# Temperature_Sensor_Rev_2.net
KiCad netlist of a schematic drawn in EAGLE
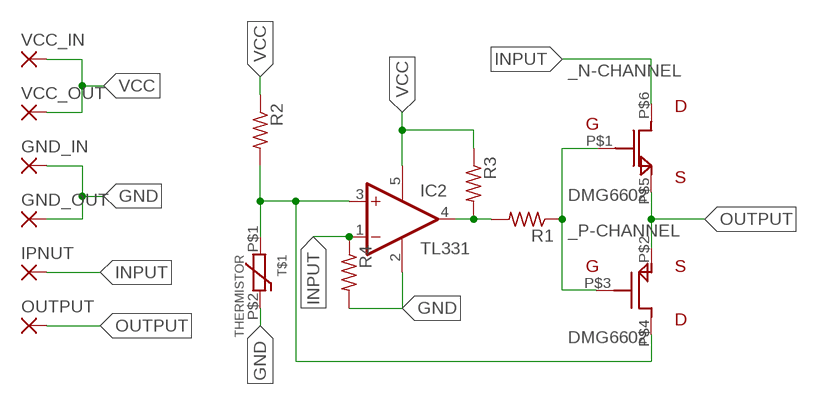
[diagram p0: schematic, sheet 1]

(export (version "E")
  (design (tool "Eeschema 10.0.6"))
  (components
    (comp (ref "GND_IN")
      (value "1,6/0,8")
      (footprint "eagle-import:1,6_0,8")
      (libsource (lib "eagle-import") (part "1,6/0,8"))
    )
    (comp (ref "GND_OUT")
      (value "1,6/0,8")
      (footprint "eagle-import:1,6_0,8")
      (libsource (lib "eagle-import") (part "1,6/0,8"))
    )
    (comp (ref "IC2")
      (value "TL331")
      (footprint "eagle-import:DBV-R-PDSO-G5")
      (libsource (lib "eagle-import") (part "TL331"))
    )
    (comp (ref "IPNUT")
      (value "1,6/0,8")
      (footprint "eagle-import:1,6_0,8")
      (libsource (lib "eagle-import") (part "1,6/0,8"))
    )
    (comp (ref "OUTPUT")
      (value "1,6/0,8")
      (footprint "eagle-import:1,6_0,8")
      (libsource (lib "eagle-import") (part "1,6/0,8"))
    )
    (comp (ref "R1")
      (value "R-US_R0603")
      (footprint "eagle-import:R0603")
      (libsource (lib "eagle-import") (part "R-US_R0603"))
    )
    (comp (ref "R2")
      (value "R-US_R0603")
      (footprint "eagle-import:R0603")
      (libsource (lib "eagle-import") (part "R-US_R0603"))
    )
    (comp (ref "R3")
      (value "R-US_R0603")
      (footprint "eagle-import:R0603")
      (libsource (lib "eagle-import") (part "R-US_R0603"))
    )
    (comp (ref "R4")
      (value "R-US_R0603")
      (footprint "eagle-import:R0603")
      (libsource (lib "eagle-import") (part "R-US_R0603"))
    )
    (comp (ref "T$1")
      (value "THERMISTOR")
      (footprint "eagle-import:0603")
      (libsource (lib "eagle-import") (part "THERMISTOR"))
    )
    (comp (ref "VCC_IN")
      (value "1,6/0,8")
      (footprint "eagle-import:1,6_0,8")
      (libsource (lib "eagle-import") (part "1,6/0,8"))
    )
    (comp (ref "VCC_OUT")
      (value "1,6/0,8")
      (footprint "eagle-import:1,6_0,8")
      (libsource (lib "eagle-import") (part "1,6/0,8"))
    )
    (comp (ref "_")
      (value "DMG6602")
      (footprint "eagle-import:SOT23-6")
      (libsource (lib "eagle-import") (part "DMG6602"))
    )
  )
  (nets
    (net (code "1") (name "GND") (class "Default")
      (node (ref "GND_IN") (pin "1") (pinfunction "P_1") (pintype "passive"))
      (node (ref "GND_OUT") (pin "1") (pinfunction "P_1") (pintype "passive"))
      (node (ref "IC2") (pin "2") (pinfunction "GND_2") (pintype "power_in"))
      (node (ref "R4") (pin "2") (pinfunction "2_2") (pintype "passive"))
      (node (ref "T$1") (pin "P$2") (pinfunction "P$2_P$2") (pintype "bidirectional"))
    )
    (net (code "2") (name "INPUT") (class "Default")
      (node (ref "IC2") (pin "1") (pinfunction "-IN_1") (pintype "input"))
      (node (ref "IPNUT") (pin "1") (pinfunction "P_1") (pintype "passive"))
      (node (ref "R4") (pin "1") (pinfunction "1_1") (pintype "passive"))
      (node (ref "_") (pin "P$6") (pinfunction "D$1_P$6") (pintype "bidirectional"))
    )
    (net (code "3") (name "Net-(IC2-+IN)") (class "Default")
      (node (ref "IC2") (pin "3") (pinfunction "+IN_3") (pintype "input"))
      (node (ref "R2") (pin "2") (pinfunction "2_2") (pintype "passive"))
      (node (ref "T$1") (pin "P$1") (pinfunction "P$1_P$1") (pintype "bidirectional"))
      (node (ref "_") (pin "P$4") (pinfunction "D$1_P$4") (pintype "bidirectional"))
    )
    (net (code "4") (name "Net-(IC2-OUT)") (class "Default")
      (node (ref "IC2") (pin "4") (pinfunction "OUT_4") (pintype "output"))
      (node (ref "R1") (pin "2") (pinfunction "2_2") (pintype "passive"))
      (node (ref "R3") (pin "2") (pinfunction "2_2") (pintype "passive"))
    )
    (net (code "5") (name "Net-(_A-G$1)") (class "Default")
      (node (ref "R1") (pin "1") (pinfunction "1_1") (pintype "passive"))
      (node (ref "_") (pin "P$1") (pinfunction "G$1_P$1") (pintype "bidirectional"))
      (node (ref "_") (pin "P$3") (pinfunction "G$1_P$3") (pintype "bidirectional"))
    )
    (net (code "6") (name "OUTPUT") (class "Default")
      (node (ref "OUTPUT") (pin "1") (pinfunction "P_1") (pintype "passive"))
      (node (ref "_") (pin "P$2") (pinfunction "S$1_P$2") (pintype "bidirectional"))
      (node (ref "_") (pin "P$5") (pinfunction "S$1_P$5") (pintype "bidirectional"))
    )
    (net (code "7") (name "VCC") (class "Default")
      (node (ref "IC2") (pin "5") (pinfunction "V+_5") (pintype "power_in"))
      (node (ref "R2") (pin "1") (pinfunction "1_1") (pintype "passive"))
      (node (ref "R3") (pin "1") (pinfunction "1_1") (pintype "passive"))
      (node (ref "VCC_IN") (pin "1") (pinfunction "P_1") (pintype "passive"))
      (node (ref "VCC_OUT") (pin "1") (pinfunction "P_1") (pintype "passive"))
    )
  )
)
